# Cortex_CLK_SWD_USB_ADC.net
KiCad netlist of a schematic drawn in Altium Designer
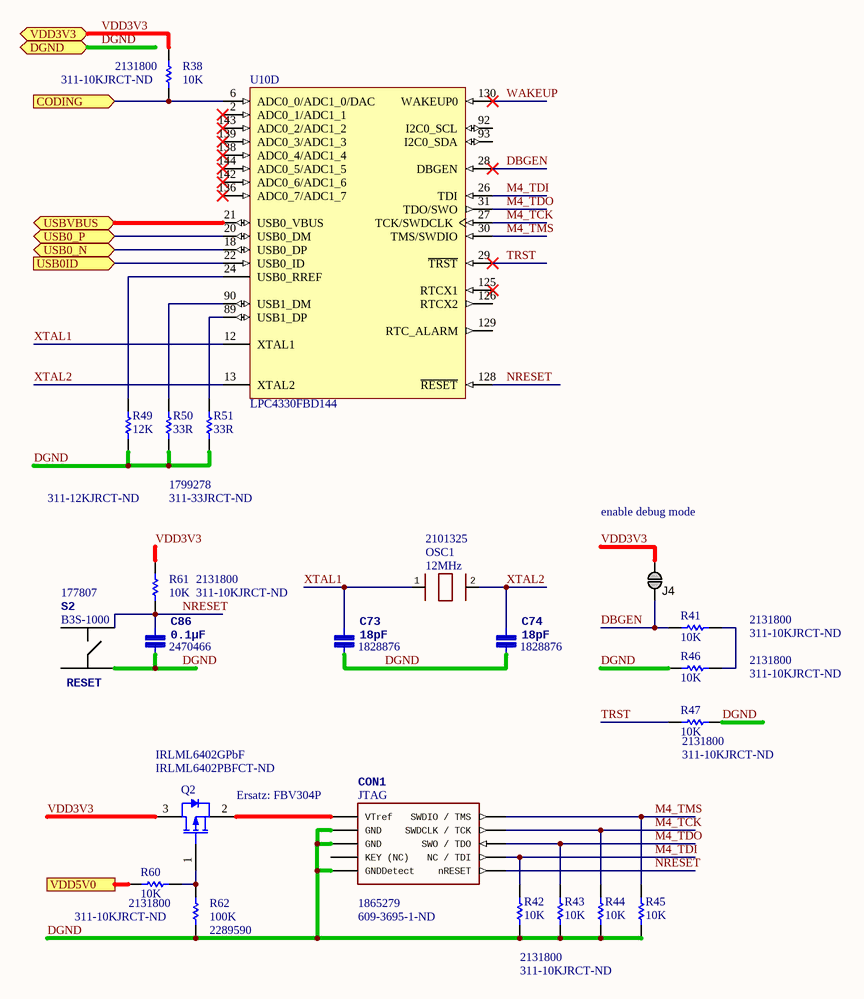
[diagram p0: Cortex CLK_SWD_USB_ADC.SchDoc]

(export (version "E")
  (design (tool "Eeschema 10.0.6"))
  (components
    (comp (ref "C73")
      (value "18pF")
      (footprint "0402[1005]")
      (description "Cap")
      (fields (field (name "SUPPLIER PART NUMBER 1") "1828876"))
      (libsource (lib "Components") (part "Capacitor"))
    )
    (comp (ref "C74")
      (value "18pF")
      (footprint "0402[1005]")
      (description "Cap")
      (fields (field (name "SUPPLIER PART NUMBER 1") "1828876"))
      (libsource (lib "Components") (part "Capacitor"))
    )
    (comp (ref "C86")
      (value "0.1µF")
      (footprint "0402[1005]")
      (description "Cap")
      (fields (field (name "SUPPLIER PART NUMBER 1") "2470466"))
      (libsource (lib "Components") (part "Capacitor"))
    )
    (comp (ref "CON1")
      (value "JTAG")
      (footprint "SWD-10-SMD")
      (fields
        (field (name "SUPPLIER PART NUMBER 1") "609-3695-1-ND")
        (field (name "SUPPLIER PART NUMBER 2") "1865279")
      )
      (libsource (lib "USD Parts") (part "SWD-10_SMD"))
    )
    (comp (ref "J4")
      (value "Jumper")
      (footprint "JUMP1")
      (description "SMD jumper")
      (libsource (lib "USD Parts") (part "JUMP1"))
    )
    (comp (ref "OSC1")
      (value "12MHz")
      (footprint "CRYSTAL_HC49-US-SM")
      (description "Resonator")
      (fields (field (name "SUPPLIER PART NUMBER 1") "2101325"))
      (libsource (lib "USD Parts") (part "Crystal 2PIN"))
    )
    (comp (ref "Q2")
      (value "IRLML6402GPbF")
      (footprint "INTR-SOT-23-3_V")
      (description "HEXFET Power MOSFET, P-Channel, -20 V VDSS, 0.065 Ohm RDS, 3-Pin SOT23, RoHS, Tape and Reel")
      (fields
        (field (name "MANUFACTURER") "International Rectifier")
        (field (name "SUPPLIER PART NUMBER 1") "IRLML6402PBFCT-ND")
      )
      (libsource (lib "Altium Content Vault") (part "INTR-PEMOS_G1S2D3-3"))
    )
    (comp (ref "R38")
      (value "10K")
      (footprint "0402[1005]")
      (description "Resistor")
      (fields
        (field (name "SUPPLIER PART NUMBER 1") "311-10KJRCT-ND")
        (field (name "SUPPLIER PART NUMBER 2") "2131800")
        (field (name "PUBLISHER") "Altium Limited")
      )
      (libsource (lib "Components") (part "Resistor"))
    )
    (comp (ref "R41")
      (value "10K")
      (footprint "0402[1005]")
      (description "Resistor")
      (fields
        (field (name "SUPPLIER PART NUMBER 1") "311-10KJRCT-ND")
        (field (name "SUPPLIER PART NUMBER 2") "2131800")
        (field (name "PUBLISHER") "Altium Limited")
      )
      (libsource (lib "USD Parts") (part "Resistor"))
    )
    (comp (ref "R42")
      (value "10K")
      (footprint "0402[1005]")
      (description "Resistor")
      (fields
        (field (name "SUPPLIER PART NUMBER 1") "311-10KJRCT-ND")
        (field (name "SUPPLIER PART NUMBER 2") "2131800")
        (field (name "PUBLISHER") "Altium Limited")
      )
      (libsource (lib "USD Parts") (part "Resistor"))
    )
    (comp (ref "R43")
      (value "10K")
      (footprint "0402[1005]")
      (description "Resistor")
      (fields (field (name "PUBLISHER") "Altium Limited"))
      (libsource (lib "USD Parts") (part "Resistor"))
    )
    (comp (ref "R44")
      (value "10K")
      (footprint "0402[1005]")
      (description "Resistor")
      (fields (field (name "PUBLISHER") "Altium Limited"))
      (libsource (lib "USD Parts") (part "Resistor"))
    )
    (comp (ref "R45")
      (value "10K")
      (footprint "0402[1005]")
      (description "Resistor")
      (fields (field (name "PUBLISHER") "Altium Limited"))
      (libsource (lib "USD Parts") (part "Resistor"))
    )
    (comp (ref "R46")
      (value "10K")
      (footprint "0402[1005]")
      (description "Resistor")
      (fields
        (field (name "SUPPLIER PART NUMBER 1") "311-10KJRCT-ND")
        (field (name "SUPPLIER PART NUMBER 2") "2131800")
        (field (name "PUBLISHER") "Altium Limited")
      )
      (libsource (lib "USD Parts") (part "Resistor"))
    )
    (comp (ref "R47")
      (value "10K")
      (footprint "0402[1005]")
      (description "Resistor")
      (fields
        (field (name "SUPPLIER PART NUMBER 1") "311-10KJRCT-ND")
        (field (name "SUPPLIER PART NUMBER 2") "2131800")
        (field (name "PUBLISHER") "Altium Limited")
      )
      (libsource (lib "USD Parts") (part "Resistor"))
    )
    (comp (ref "R49")
      (value "12K")
      (footprint "0402[1005]")
      (description "Resistor")
      (fields
        (field (name "SUPPLIER PART NUMBER 1") "311-12KJRCT-ND")
        (field (name "PUBLISHER") "Altium Limited")
      )
      (libsource (lib "Components") (part "Resistor"))
    )
    (comp (ref "R50")
      (value "33R")
      (footprint "0402[1005]")
      (description "Resistor")
      (fields
        (field (name "SUPPLIER PART NUMBER 1") "311-33JRCT-ND")
        (field (name "SUPPLIER PART NUMBER 2") "1799278")
        (field (name "PUBLISHER") "Altium Limited")
      )
      (libsource (lib "Components") (part "Resistor"))
    )
    (comp (ref "R51")
      (value "33R")
      (footprint "0402[1005]")
      (description "Resistor")
      (fields (field (name "PUBLISHER") "Altium Limited"))
      (libsource (lib "Components") (part "Resistor"))
    )
    (comp (ref "R60")
      (value "10K")
      (footprint "0402[1005]")
      (description "Resistor")
      (fields
        (field (name "SUPPLIER PART NUMBER 1") "311-10KJRCT-ND")
        (field (name "SUPPLIER PART NUMBER 2") "2131800")
        (field (name "PUBLISHER") "Altium Limited")
      )
      (libsource (lib "USD Parts") (part "Resistor"))
    )
    (comp (ref "R61")
      (value "10K")
      (footprint "0402[1005]")
      (description "Resistor")
      (fields
        (field (name "SUPPLIER PART NUMBER 1") "311-10KJRCT-ND")
        (field (name "SUPPLIER PART NUMBER 2") "2131800")
        (field (name "PUBLISHER") "Altium Limited")
      )
      (libsource (lib "USD Parts") (part "Resistor"))
    )
    (comp (ref "R62")
      (value "100K")
      (footprint "0402[1005]")
      (description "Resistor")
      (fields (field (name "SUPPLIER PART NUMBER 1") "2289590") (field (name "PUBLISHER") "Altium Limited"))
      (libsource (lib "USD Parts") (part "Resistor"))
    )
    (comp (ref "S2")
      (value "RESET")
      (footprint "Omron B3S1000")
      (description "Sealed Tactile Switch (SMT)")
      (fields (field (name "ALTIUM_VALUE") "B3S-1000") (field (name "SUPPLIER PART NUMBER 1") "177807"))
      (libsource (lib "USD Parts") (part "B3S-1000"))
    )
    (comp (ref "U10")
      (value "LPC4330FBD144")
      (footprint "LQFP144")
      (libsource (lib "USD Parts") (part "LPC4330FBD144"))
    )
  )
  (nets
    (net (code "1") (name "/CODING") (class "Default")
      (node (ref "R38") (pin "2") (pinfunction "2_2") (pintype "passive"))
      (node (ref "U10") (pin "6") (pinfunction "ADC0_0/ADC1_0/DAC_6") (pintype "input"))
    )
    (net (code "2") (name "/DBGEN") (class "Default")
      (node (ref "J4") (pin "2") (pintype "passive"))
      (node (ref "R41") (pin "1") (pinfunction "1_1") (pintype "passive"))
      (node (ref "U10") (pin "28") (pinfunction "DBGEN_28") (pintype "input"))
    )
    (net (code "3") (name "/DGND") (class "Default")
      (node (ref "C73") (pin "2") (pinfunction "P$2_2") (pintype "passive"))
      (node (ref "C74") (pin "2") (pinfunction "P$2_2") (pintype "passive"))
      (node (ref "C86") (pin "2") (pinfunction "P$2_2") (pintype "passive"))
      (node (ref "CON1") (pin "GND") (pinfunction "GND_GND") (pintype "passive"))
      (node (ref "CON1") (pin "GNDDetect") (pinfunction "GNDDetect_GNDDetect") (pintype "passive"))
      (node (ref "R42") (pin "2") (pinfunction "2_2") (pintype "passive"))
      (node (ref "R43") (pin "2") (pinfunction "2_2") (pintype "passive"))
      (node (ref "R44") (pin "2") (pinfunction "2_2") (pintype "passive"))
      (node (ref "R45") (pin "2") (pinfunction "2_2") (pintype "passive"))
      (node (ref "R46") (pin "2") (pinfunction "2_2") (pintype "passive"))
      (node (ref "R47") (pin "2") (pinfunction "2_2") (pintype "passive"))
      (node (ref "R49") (pin "2") (pinfunction "2_2") (pintype "passive"))
      (node (ref "R50") (pin "2") (pinfunction "2_2") (pintype "passive"))
      (node (ref "R51") (pin "2") (pinfunction "2_2") (pintype "passive"))
      (node (ref "R62") (pin "1") (pinfunction "1_1") (pintype "passive"))
      (node (ref "S2") (pin "1") (pinfunction "1_1") (pintype "passive"))
    )
    (net (code "4") (name "/M4_TCK") (class "Default")
      (node (ref "CON1") (pin "TCK") (pinfunction "SWDCLK_/_TCK_TCK") (pintype "output"))
      (node (ref "R44") (pin "1") (pinfunction "1_1") (pintype "passive"))
      (node (ref "U10") (pin "27") (pinfunction "TCK/SWDCLK_27") (pintype "input"))
    )
    (net (code "5") (name "/M4_TDI") (class "Default")
      (node (ref "CON1") (pin "TDI") (pinfunction "NC_/_TDI_TDI") (pintype "output"))
      (node (ref "R42") (pin "1") (pinfunction "1_1") (pintype "passive"))
      (node (ref "U10") (pin "26") (pinfunction "TDI_26") (pintype "input"))
    )
    (net (code "6") (name "/M4_TDO") (class "Default")
      (node (ref "CON1") (pin "TDO") (pinfunction "SWO_/_TDO_TDO") (pintype "input"))
      (node (ref "R43") (pin "1") (pinfunction "1_1") (pintype "passive"))
      (node (ref "U10") (pin "31") (pinfunction "TDO/SWO_31") (pintype "output"))
    )
    (net (code "7") (name "/M4_TMS") (class "Default")
      (node (ref "CON1") (pin "TMS") (pinfunction "SWDIO_/_TMS_TMS") (pintype "output"))
      (node (ref "R45") (pin "1") (pinfunction "1_1") (pintype "passive"))
      (node (ref "U10") (pin "30") (pinfunction "TMS/SWDIO_30") (pintype "input"))
    )
    (net (code "8") (name "/NRESET") (class "Default")
      (node (ref "C86") (pin "1") (pinfunction "P$1_1") (pintype "passive"))
      (node (ref "CON1") (pin "nRESET") (pinfunction "nRESET_nRESET") (pintype "output"))
      (node (ref "R61") (pin "2") (pinfunction "2_2") (pintype "passive"))
      (node (ref "S2") (pin "3") (pinfunction "3_3") (pintype "passive"))
      (node (ref "U10") (pin "128") (pinfunction "~{RESET}_128") (pintype "input"))
    )
    (net (code "9") (name "/TRST") (class "Default")
      (node (ref "R47") (pin "1") (pinfunction "1_1") (pintype "passive"))
      (node (ref "U10") (pin "29") (pinfunction "~{TRST}_29") (pintype "input"))
    )
    (net (code "10") (name "/USB0ID") (class "Default")
      (node (ref "U10") (pin "22") (pinfunction "USB0_ID_22") (pintype "input"))
    )
    (net (code "11") (name "/USB0_N") (class "Default")
      (node (ref "U10") (pin "18") (pinfunction "USB0_DP_18") (pintype "bidirectional"))
    )
    (net (code "12") (name "/USB0_P") (class "Default")
      (node (ref "U10") (pin "20") (pinfunction "USB0_DM_20") (pintype "bidirectional"))
    )
    (net (code "13") (name "/USBVBUS") (class "Default")
      (node (ref "U10") (pin "21") (pinfunction "USB0_VBUS_21") (pintype "bidirectional"))
    )
    (net (code "14") (name "/VDD3V3") (class "Default")
      (node (ref "J4") (pin "1") (pintype "passive"))
      (node (ref "Q2") (pin "3") (pinfunction "D_3") (pintype "passive"))
      (node (ref "R38") (pin "1") (pinfunction "1_1") (pintype "passive"))
      (node (ref "R61") (pin "1") (pinfunction "1_1") (pintype "passive"))
    )
    (net (code "15") (name "/VDD5V0") (class "Default")
      (node (ref "R60") (pin "1") (pinfunction "1_1") (pintype "passive"))
    )
    (net (code "16") (name "/WAKEUP") (class "Default")
      (node (ref "U10") (pin "130") (pinfunction "WAKEUP0_130") (pintype "input+no_connect"))
    )
    (net (code "17") (name "/XTAL1") (class "Default")
      (node (ref "C73") (pin "1") (pinfunction "P$1_1") (pintype "passive"))
      (node (ref "OSC1") (pin "1") (pinfunction "1_1") (pintype "passive"))
      (node (ref "U10") (pin "12") (pinfunction "XTAL1_12") (pintype "passive"))
    )
    (net (code "18") (name "/XTAL2") (class "Default")
      (node (ref "C74") (pin "1") (pinfunction "P$1_1") (pintype "passive"))
      (node (ref "OSC1") (pin "2") (pinfunction "2_2") (pintype "passive"))
      (node (ref "U10") (pin "13") (pinfunction "XTAL2_13") (pintype "passive"))
    )
    (net (code "19") (name "Net-(Q2-G)") (class "Default")
      (node (ref "Q2") (pin "1") (pinfunction "G_1") (pintype "passive"))
      (node (ref "R60") (pin "2") (pinfunction "2_2") (pintype "passive"))
      (node (ref "R62") (pin "2") (pinfunction "2_2") (pintype "passive"))
    )
    (net (code "20") (name "Net-(Q2-S)") (class "Default")
      (node (ref "CON1") (pin "VTref") (pinfunction "VTref_VTref") (pintype "passive"))
      (node (ref "Q2") (pin "2") (pinfunction "S_2") (pintype "passive"))
    )
    (net (code "21") (name "Net-(R41-Pad2)") (class "Default")
      (node (ref "R41") (pin "2") (pinfunction "2_2") (pintype "passive"))
      (node (ref "R46") (pin "1") (pinfunction "1_1") (pintype "passive"))
    )
    (net (code "22") (name "Net-(U10D-USB0_RREF)") (class "Default")
      (node (ref "R49") (pin "1") (pinfunction "1_1") (pintype "passive"))
      (node (ref "U10") (pin "24") (pinfunction "USB0_RREF_24") (pintype "passive"))
    )
    (net (code "23") (name "Net-(U10D-USB1_DM)") (class "Default")
      (node (ref "R50") (pin "1") (pinfunction "1_1") (pintype "passive"))
      (node (ref "U10") (pin "90") (pinfunction "USB1_DM_90") (pintype "bidirectional"))
    )
    (net (code "24") (name "Net-(U10D-USB1_DP)") (class "Default")
      (node (ref "R51") (pin "1") (pinfunction "1_1") (pintype "passive"))
      (node (ref "U10") (pin "89") (pinfunction "USB1_DP_89") (pintype "bidirectional"))
    )
    (net (code "25") (name "unconnected-(CON1-KEY_(NC)-PadKEY)") (class "Default")
      (node (ref "CON1") (pin "KEY") (pinfunction "KEY_(NC)_KEY") (pintype "passive"))
    )
    (net (code "26") (name "unconnected-(S2-Pad2)") (class "Default")
      (node (ref "S2") (pin "2") (pinfunction "2_2") (pintype "passive"))
    )
    (net (code "27") (name "unconnected-(S2-Pad4)") (class "Default")
      (node (ref "S2") (pin "4") (pinfunction "4_4") (pintype "passive"))
    )
    (net (code "28") (name "unconnected-(U10D-ADC0_1{slash}ADC1_1-Pad2)") (class "Default")
      (node (ref "U10") (pin "2") (pinfunction "ADC0_1/ADC1_1_2") (pintype "input+no_connect"))
    )
    (net (code "29") (name "unconnected-(U10D-ADC0_2{slash}ADC1_2-Pad143)") (class "Default")
      (node (ref "U10") (pin "143") (pinfunction "ADC0_2/ADC1_2_143") (pintype "input+no_connect"))
    )
    (net (code "30") (name "unconnected-(U10D-ADC0_3{slash}ADC1_3-Pad139)") (class "Default")
      (node (ref "U10") (pin "139") (pinfunction "ADC0_3/ADC1_3_139") (pintype "input+no_connect"))
    )
    (net (code "31") (name "unconnected-(U10D-ADC0_4{slash}ADC1_4-Pad138)") (class "Default")
      (node (ref "U10") (pin "138") (pinfunction "ADC0_4/ADC1_4_138") (pintype "input+no_connect"))
    )
    (net (code "32") (name "unconnected-(U10D-ADC0_5{slash}ADC1_5-Pad144)") (class "Default")
      (node (ref "U10") (pin "144") (pinfunction "ADC0_5/ADC1_5_144") (pintype "input+no_connect"))
    )
    (net (code "33") (name "unconnected-(U10D-ADC0_6{slash}ADC1_6-Pad142)") (class "Default")
      (node (ref "U10") (pin "142") (pinfunction "ADC0_6/ADC1_6_142") (pintype "input+no_connect"))
    )
    (net (code "34") (name "unconnected-(U10D-ADC0_7{slash}ADC1_7-Pad136)") (class "Default")
      (node (ref "U10") (pin "136") (pinfunction "ADC0_7/ADC1_7_136") (pintype "input+no_connect"))
    )
    (net (code "35") (name "unconnected-(U10D-I2C0_SCL-Pad92)") (class "Default")
      (node (ref "U10") (pin "92") (pinfunction "I2C0_SCL_92") (pintype "bidirectional"))
    )
    (net (code "36") (name "unconnected-(U10D-I2C0_SDA-Pad93)") (class "Default")
      (node (ref "U10") (pin "93") (pinfunction "I2C0_SDA_93") (pintype "bidirectional"))
    )
    (net (code "37") (name "unconnected-(U10D-RTCX1-Pad125)") (class "Default")
      (node (ref "U10") (pin "125") (pinfunction "RTCX1_125") (pintype "input+no_connect"))
    )
    (net (code "38") (name "unconnected-(U10D-RTCX2-Pad126)") (class "Default")
      (node (ref "U10") (pin "126") (pinfunction "RTCX2_126") (pintype "output"))
    )
    (net (code "39") (name "unconnected-(U10D-RTC_ALARM-Pad129)") (class "Default")
      (node (ref "U10") (pin "129") (pinfunction "RTC_ALARM_129") (pintype "output"))
    )
  )
)
